# 3_SurvBot_RCU_MotorControl.net
KiCad netlist of a schematic drawn in Altium Designer
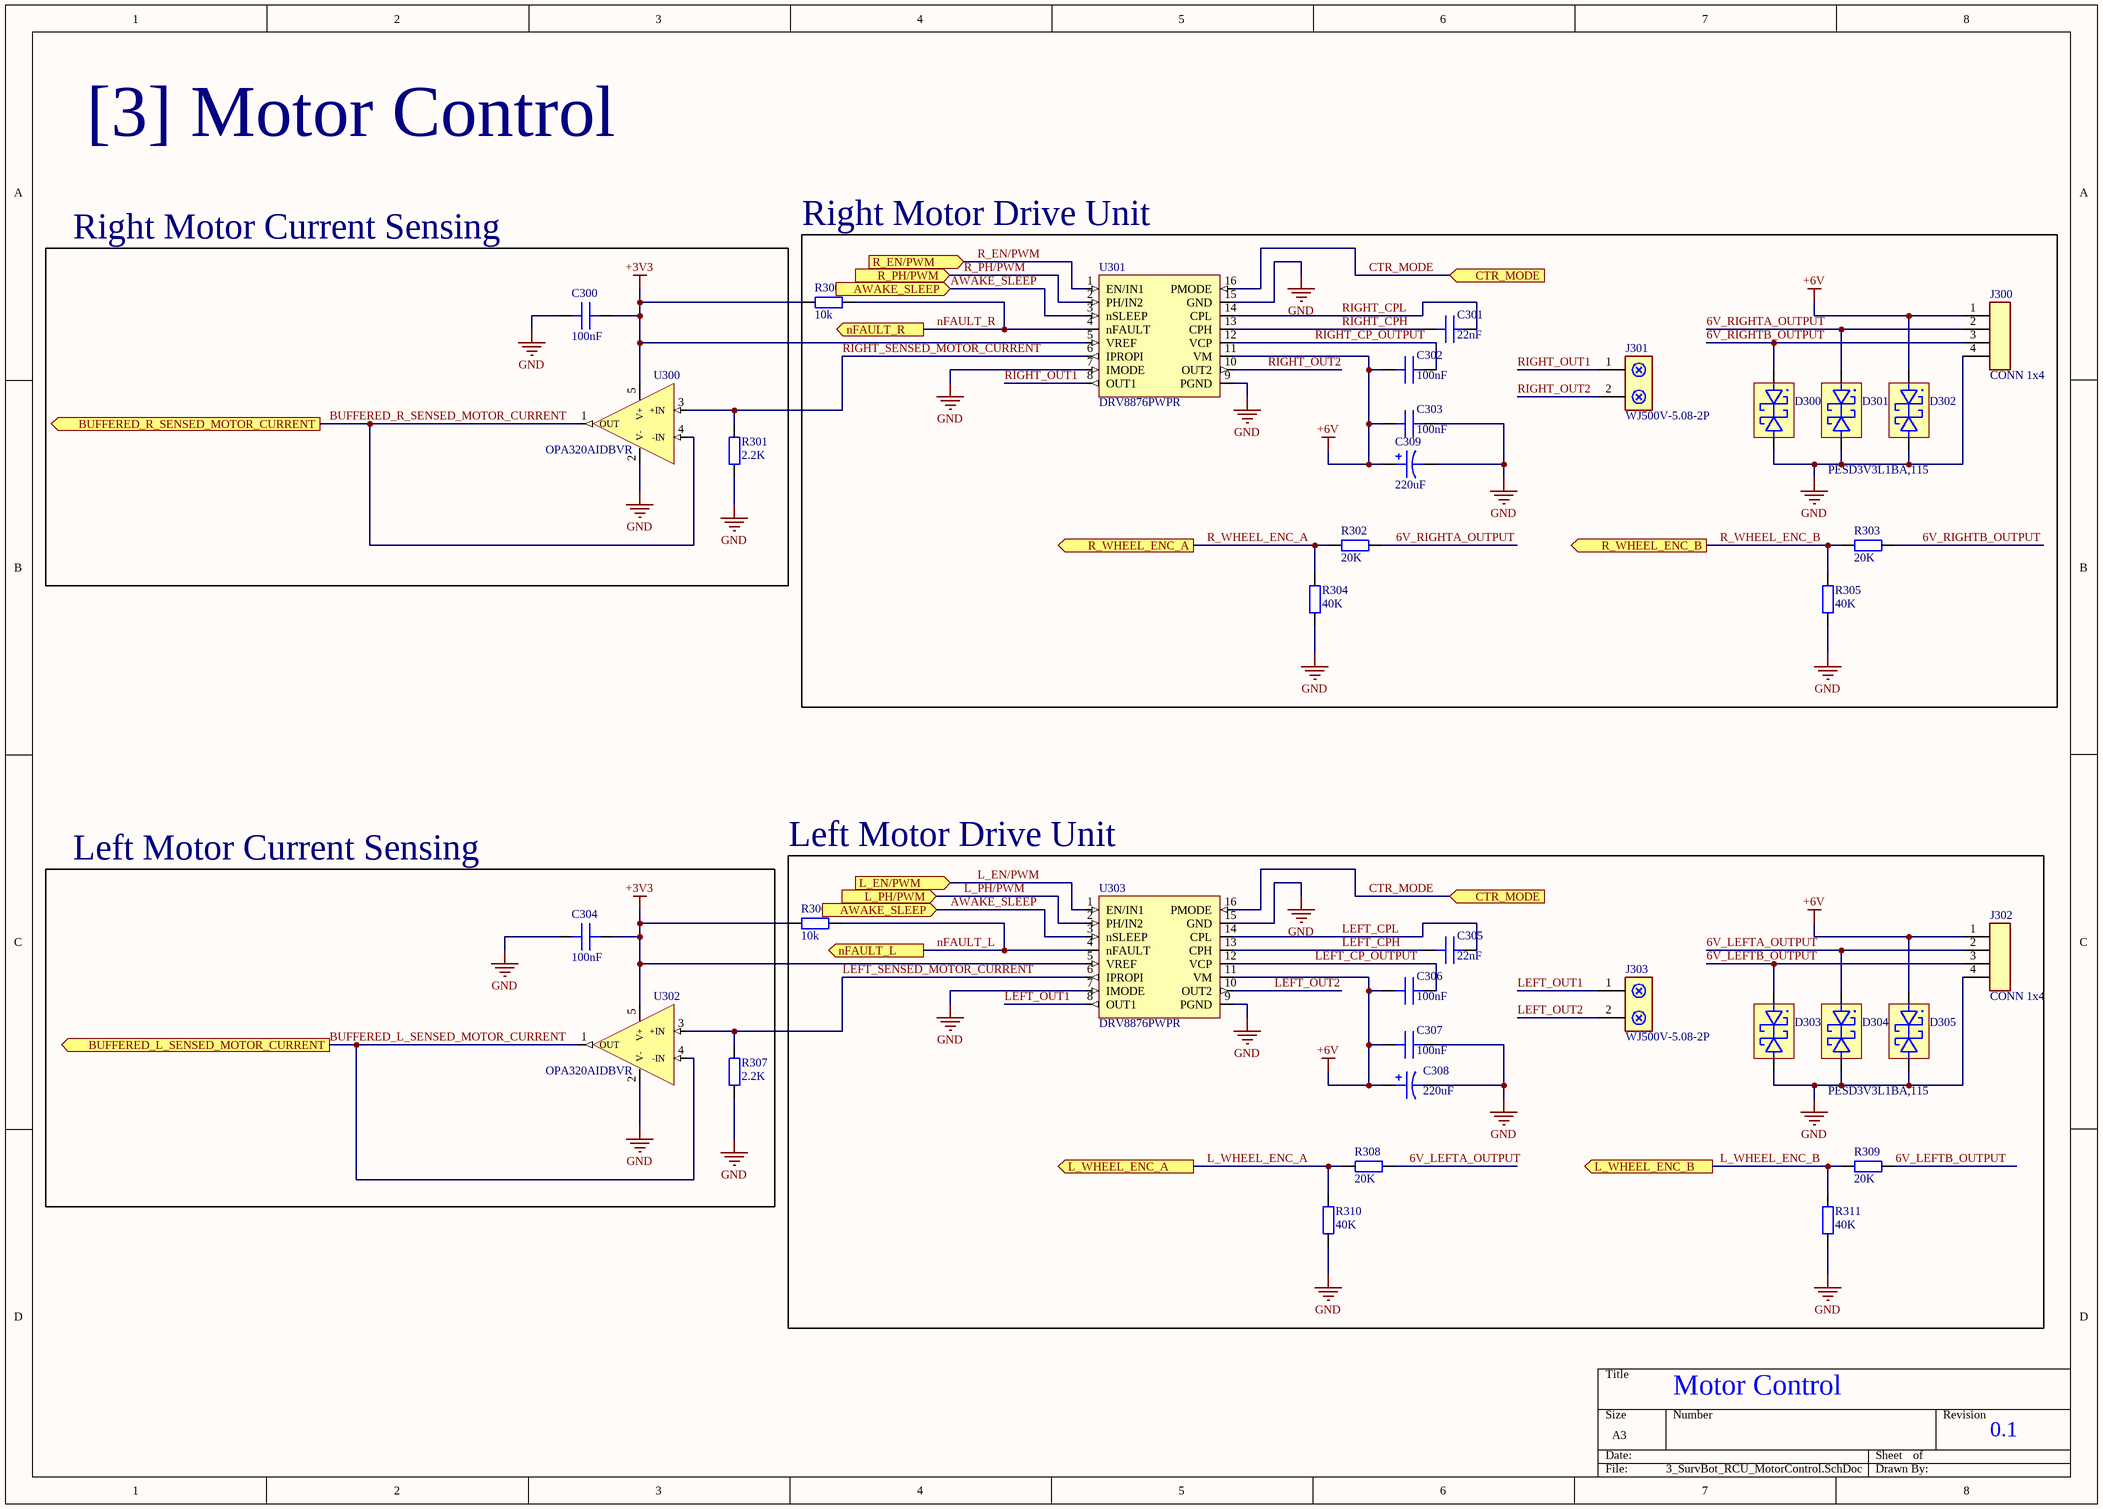
[diagram p0: 3_SurvBot_RCU_MotorControl.SchDoc]

(export (version "E")
  (design (tool "Eeschema 10.0.6"))
  (components
    (comp (ref "C300")
      (value "100nF")
      (footprint "CAP_0603")
      (description "0.1 µF ±10% 50V Ceramic Capacitor X7R 0603 (1608 Metric)")
      (fields (field (name "MANUFACTURER") "KEMET") (field (name "MANUFACTURER PART #") "C0603C104K5RACAUTO"))
      (libsource (lib "GhaniLibrary") (part "CAP_100nF-50V-10%-0603"))
    )
    (comp (ref "C301")
      (value "22nF")
      (footprint "CAP_0603")
      (description "0.022 µF ±10% 100V Ceramic Capacitor X7R 0603 (1608 Metric)")
      (fields
        (field (name "MANUFACTURER") "Murata Electronics")
        (field (name "MANUFACTURER PART #") "GCM188R72A223KA37D")
      )
      (libsource (lib "GhaniLibrary") (part "CAP_22nF_100V-10%-0603"))
    )
    (comp (ref "C302")
      (value "100nF")
      (footprint "CAP_0603")
      (description "0.1 µF ±10% 50V Ceramic Capacitor X7R 0603 (1608 Metric)")
      (fields (field (name "MANUFACTURER") "KEMET") (field (name "MANUFACTURER PART #") "C0603C104K5RACAUTO"))
      (libsource (lib "GhaniLibrary") (part "CAP_100nF-50V-10%-0603"))
    )
    (comp (ref "C303")
      (value "100nF")
      (footprint "CAP_0603")
      (description "0.1 µF ±10% 50V Ceramic Capacitor X7R 0603 (1608 Metric)")
      (fields (field (name "MANUFACTURER") "KEMET") (field (name "MANUFACTURER PART #") "C0603C104K5RACAUTO"))
      (libsource (lib "GhaniLibrary") (part "CAP_100nF-50V-10%-0603"))
    )
    (comp (ref "C304")
      (value "100nF")
      (footprint "CAP_0603")
      (description "0.1 µF ±10% 50V Ceramic Capacitor X7R 0603 (1608 Metric)")
      (fields (field (name "MANUFACTURER") "KEMET") (field (name "MANUFACTURER PART #") "C0603C104K5RACAUTO"))
      (libsource (lib "GhaniLibrary") (part "CAP_100nF-50V-10%-0603"))
    )
    (comp (ref "C305")
      (value "22nF")
      (footprint "CAP_0603")
      (description "0.022 µF ±10% 100V Ceramic Capacitor X7R 0603 (1608 Metric)")
      (fields
        (field (name "MANUFACTURER") "Murata Electronics")
        (field (name "MANUFACTURER PART #") "GCM188R72A223KA37D")
      )
      (libsource (lib "GhaniLibrary") (part "CAP_22nF_100V-10%-0603"))
    )
    (comp (ref "C306")
      (value "100nF")
      (footprint "CAP_0603")
      (description "0.1 µF ±10% 50V Ceramic Capacitor X7R 0603 (1608 Metric)")
      (fields (field (name "MANUFACTURER") "KEMET") (field (name "MANUFACTURER PART #") "C0603C104K5RACAUTO"))
      (libsource (lib "GhaniLibrary") (part "CAP_100nF-50V-10%-0603"))
    )
    (comp (ref "C307")
      (value "100nF")
      (footprint "CAP_0603")
      (description "0.1 µF ±10% 50V Ceramic Capacitor X7R 0603 (1608 Metric)")
      (fields (field (name "MANUFACTURER") "KEMET") (field (name "MANUFACTURER PART #") "C0603C104K5RACAUTO"))
      (libsource (lib "GhaniLibrary") (part "CAP_100nF-50V-10%-0603"))
    )
    (comp (ref "C308")
      (value "220uF")
      (footprint "CAP-THT-Radial__D8.0mmP3.5mm")
      (description "220 µF 35 V Aluminum Electrolytic Capacitors Radial, Can 8000 Hrs @ 105°C")
      (fields
        (field (name "MANUFACTURER") "Rubycon")
        (field (name "MANUFACTURER PART #") "35ZLH220MEFC8X11.5")
      )
      (libsource (lib "GhaniLibrary") (part "CAP_220uF-35V-20%_RADIAL-TH"))
    )
    (comp (ref "C309")
      (value "220uF")
      (footprint "CAP-THT-Radial__D8.0mmP3.5mm")
      (description "220 µF 35 V Aluminum Electrolytic Capacitors Radial, Can 8000 Hrs @ 105°C")
      (fields
        (field (name "MANUFACTURER") "Rubycon")
        (field (name "MANUFACTURER PART #") "35ZLH220MEFC8X11.5")
      )
      (libsource (lib "GhaniLibrary") (part "CAP_220uF-35V-20%_RADIAL-TH"))
    )
    (comp (ref "D300")
      (value "PESD3V3L1BA,115")
      (footprint "SC-76, SOD-323")
      (description "26V Clamp 18A (8/20µs) Ipp Tvs Diode Surface Mount SOD-323")
      (fields (field (name "MANUFACTURER") "Nexperia"))
      (libsource (lib "GhaniLibrary") (part "DIO-TVS_3.3V-26V-18A-SOD-323"))
    )
    (comp (ref "D301")
      (value "PESD3V3L1BA,115")
      (footprint "SC-76, SOD-323")
      (description "26V Clamp 18A (8/20µs) Ipp Tvs Diode Surface Mount SOD-323")
      (fields (field (name "MANUFACTURER") "Nexperia"))
      (libsource (lib "GhaniLibrary") (part "DIO-TVS_3.3V-26V-18A-SOD-323"))
    )
    (comp (ref "D302")
      (value "PESD3V3L1BA,115")
      (footprint "SC-76, SOD-323")
      (description "26V Clamp 18A (8/20µs) Ipp Tvs Diode Surface Mount SOD-323")
      (fields (field (name "MANUFACTURER") "Nexperia"))
      (libsource (lib "GhaniLibrary") (part "DIO-TVS_3.3V-26V-18A-SOD-323"))
    )
    (comp (ref "D303")
      (value "PESD3V3L1BA,115")
      (footprint "SC-76, SOD-323")
      (description "26V Clamp 18A (8/20µs) Ipp Tvs Diode Surface Mount SOD-323")
      (fields (field (name "MANUFACTURER") "Nexperia"))
      (libsource (lib "GhaniLibrary") (part "DIO-TVS_3.3V-26V-18A-SOD-323"))
    )
    (comp (ref "D304")
      (value "PESD3V3L1BA,115")
      (footprint "SC-76, SOD-323")
      (description "26V Clamp 18A (8/20µs) Ipp Tvs Diode Surface Mount SOD-323")
      (fields (field (name "MANUFACTURER") "Nexperia"))
      (libsource (lib "GhaniLibrary") (part "DIO-TVS_3.3V-26V-18A-SOD-323"))
    )
    (comp (ref "D305")
      (value "PESD3V3L1BA,115")
      (footprint "SC-76, SOD-323")
      (description "26V Clamp 18A (8/20µs) Ipp Tvs Diode Surface Mount SOD-323")
      (fields (field (name "MANUFACTURER") "Nexperia"))
      (libsource (lib "GhaniLibrary") (part "DIO-TVS_3.3V-26V-18A-SOD-323"))
    )
    (comp (ref "J300")
      (value "CONN 1x4")
      (footprint "2541FV-4P")
      (fields (field (name "MANUFACTURER") "HanElectricity") (field (name "MANUFACTURER PART #") "2541FV-4P"))
      (libsource (lib "GhaniLibrary") (part "CONN_4_HDR_0.1-2541FV-4P"))
    )
    (comp (ref "J301")
      (value "WJ500V-5.08-2P")
      (footprint "WJ500V-5.08-2P")
      (fields (field (name "MANUFACTURER") "Ningbo Kangnex Elec"))
      (libsource (lib "GhaniLibrary") (part "Terminal_Screw_5.08mm_2P"))
    )
    (comp (ref "J302")
      (value "CONN 1x4")
      (footprint "2541FV-4P")
      (fields (field (name "MANUFACTURER") "HanElectricity") (field (name "MANUFACTURER PART #") "2541FV-4P"))
      (libsource (lib "GhaniLibrary") (part "CONN_4_HDR_0.1-2541FV-4P"))
    )
    (comp (ref "J303")
      (value "WJ500V-5.08-2P")
      (footprint "WJ500V-5.08-2P")
      (fields (field (name "MANUFACTURER") "Ningbo Kangnex Elec"))
      (libsource (lib "GhaniLibrary") (part "Terminal_Screw_5.08mm_2P"))
    )
    (comp (ref "R300")
      (value "10k")
      (footprint "RES_0402")
      (description "10 kOhms ±1% 0.063W, 1/16W Chip Resistor 0402 (1005 Metric) Moisture Resistant Thick Film")
      (fields (field (name "MANUFACTURER") "YAGEO") (field (name "MANUFACTURER PART #") "RC0402FR-0710KL"))
      (libsource (lib "GhaniLibrary") (part "RES_10K-62.5mW-1%-0402"))
    )
    (comp (ref "R301")
      (value "2.2K")
      (footprint "RES_0603")
      (description "2.2 kOhms ±1% 0.1W, 1/10W Chip Resistor 0603 (1608 Metric) Moisture Resistant Thick Film")
      (fields (field (name "MANUFACTURER") "YAGEO") (field (name "MANUFACTURER PART #") "RC0603FR-072K2L"))
      (libsource (lib "GhaniLibrary") (part "RES_2.2K-100mW-1%-0603"))
    )
    (comp (ref "R302")
      (value "20K")
      (footprint "RES_0603")
      (description "20 kOhms ±1% 0.1W, 1/10W Chip Resistor 0603 (1608 Metric) Automotive AEC-Q200 Thick Film")
      (fields (field (name "MANUFACTURER") "PANASONIC") (field (name "MANUFACTURER PART #") "ERJ-3EKF2002V"))
      (libsource (lib "GhaniLibrary") (part "RES_20K-100mW-1%-0603"))
    )
    (comp (ref "R303")
      (value "20K")
      (footprint "RES_0603")
      (description "20 kOhms ±1% 0.1W, 1/10W Chip Resistor 0603 (1608 Metric) Automotive AEC-Q200 Thick Film")
      (fields (field (name "MANUFACTURER") "PANASONIC") (field (name "MANUFACTURER PART #") "ERJ-3EKF2002V"))
      (libsource (lib "GhaniLibrary") (part "RES_20K-100mW-1%-0603"))
    )
    (comp (ref "R304")
      (value "40K")
      (footprint "RES_0603")
      (fields (field (name "MANUFACTURER") "YAGEO") (field (name "MANUFACTURER PART #") "AT0603BRD0740KL"))
      (libsource (lib "GhaniLibrary") (part "RES_40K_100mW-1%-0603"))
    )
    (comp (ref "R305")
      (value "40K")
      (footprint "RES_0603")
      (fields (field (name "MANUFACTURER") "YAGEO") (field (name "MANUFACTURER PART #") "AT0603BRD0740KL"))
      (libsource (lib "GhaniLibrary") (part "RES_40K_100mW-1%-0603"))
    )
    (comp (ref "R306")
      (value "10k")
      (footprint "RES_0402")
      (description "10 kOhms ±1% 0.063W, 1/16W Chip Resistor 0402 (1005 Metric) Moisture Resistant Thick Film")
      (fields (field (name "MANUFACTURER") "YAGEO") (field (name "MANUFACTURER PART #") "RC0402FR-0710KL"))
      (libsource (lib "GhaniLibrary") (part "RES_10K-62.5mW-1%-0402"))
    )
    (comp (ref "R307")
      (value "2.2K")
      (footprint "RES_0603")
      (description "2.2 kOhms ±1% 0.1W, 1/10W Chip Resistor 0603 (1608 Metric) Moisture Resistant Thick Film")
      (fields (field (name "MANUFACTURER") "YAGEO") (field (name "MANUFACTURER PART #") "RC0603FR-072K2L"))
      (libsource (lib "GhaniLibrary") (part "RES_2.2K-100mW-1%-0603"))
    )
    (comp (ref "R308")
      (value "20K")
      (footprint "RES_0603")
      (description "20 kOhms ±1% 0.1W, 1/10W Chip Resistor 0603 (1608 Metric) Automotive AEC-Q200 Thick Film")
      (fields (field (name "MANUFACTURER") "PANASONIC") (field (name "MANUFACTURER PART #") "ERJ-3EKF2002V"))
      (libsource (lib "GhaniLibrary") (part "RES_20K-100mW-1%-0603"))
    )
    (comp (ref "R309")
      (value "20K")
      (footprint "RES_0603")
      (description "20 kOhms ±1% 0.1W, 1/10W Chip Resistor 0603 (1608 Metric) Automotive AEC-Q200 Thick Film")
      (fields (field (name "MANUFACTURER") "PANASONIC") (field (name "MANUFACTURER PART #") "ERJ-3EKF2002V"))
      (libsource (lib "GhaniLibrary") (part "RES_20K-100mW-1%-0603"))
    )
    (comp (ref "R310")
      (value "40K")
      (footprint "RES_0603")
      (fields (field (name "MANUFACTURER") "YAGEO") (field (name "MANUFACTURER PART #") "AT0603BRD0740KL"))
      (libsource (lib "GhaniLibrary") (part "RES_40K_100mW-1%-0603"))
    )
    (comp (ref "R311")
      (value "40K")
      (footprint "RES_0603")
      (fields (field (name "MANUFACTURER") "YAGEO") (field (name "MANUFACTURER PART #") "AT0603BRD0740KL"))
      (libsource (lib "GhaniLibrary") (part "RES_40K_100mW-1%-0603"))
    )
    (comp (ref "U300")
      (value "OPA320AIDBVR")
      (footprint "SOT-23-5")
      (description "General Purpose Amplifier 1 Circuit Rail-to-Rail SOT-23-5")
      (fields (field (name "MANUFACTURER") "Texas Instruments"))
      (libsource (lib "GhaniLibrary") (part "OPAMP-OPA320_R2R_SOT23-5"))
    )
    (comp (ref "U301")
      (value "DRV8876PWPR")
      (footprint "16-HTSSOP")
      (description "DRV8876 H-Bridge Motor Driver With Integrated Current Sense and Regulation 16-HTSSOP")
      (fields (field (name "MANUFACTURER") "Texas Instruments"))
      (libsource (lib "GhaniLibrary") (part "MTRDRV-DRV8876-HBridge_4.5-37V_3.5A"))
    )
    (comp (ref "U302")
      (value "OPA320AIDBVR")
      (footprint "SOT-23-5")
      (description "General Purpose Amplifier 1 Circuit Rail-to-Rail SOT-23-5")
      (fields (field (name "MANUFACTURER") "Texas Instruments"))
      (libsource (lib "GhaniLibrary") (part "OPAMP-OPA320_R2R_SOT23-5"))
    )
    (comp (ref "U303")
      (value "DRV8876PWPR")
      (footprint "16-HTSSOP")
      (description "DRV8876 H-Bridge Motor Driver With Integrated Current Sense and Regulation 16-HTSSOP")
      (fields (field (name "MANUFACTURER") "Texas Instruments"))
      (libsource (lib "GhaniLibrary") (part "MTRDRV-DRV8876-HBridge_4.5-37V_3.5A"))
    )
  )
  (nets
    (net (code "1") (name "+3V3") (class "Default")
      (node (ref "C300") (pin "1") (pinfunction "0_1") (pintype "passive"))
      (node (ref "C304") (pin "1") (pinfunction "0_1") (pintype "passive"))
      (node (ref "R300") (pin "1") (pinfunction "1_1") (pintype "passive"))
      (node (ref "R306") (pin "1") (pinfunction "1_1") (pintype "passive"))
      (node (ref "U300") (pin "5") (pinfunction "V+_5") (pintype "power_in"))
      (node (ref "U301") (pin "5") (pinfunction "VREF_5") (pintype "input"))
      (node (ref "U302") (pin "5") (pinfunction "V+_5") (pintype "power_in"))
      (node (ref "U303") (pin "5") (pinfunction "VREF_5") (pintype "input"))
    )
    (net (code "2") (name "+6V") (class "Default")
      (node (ref "C302") (pin "2") (pinfunction "0_2") (pintype "passive"))
      (node (ref "C303") (pin "2") (pinfunction "0_2") (pintype "passive"))
      (node (ref "C306") (pin "2") (pinfunction "0_2") (pintype "passive"))
      (node (ref "C307") (pin "2") (pinfunction "0_2") (pintype "passive"))
      (node (ref "C308") (pin "1") (pinfunction "0_1") (pintype "passive"))
      (node (ref "C309") (pin "1") (pinfunction "0_1") (pintype "passive"))
      (node (ref "D302") (pin "K1") (pinfunction "1_K1") (pintype "passive"))
      (node (ref "D305") (pin "K1") (pinfunction "1_K1") (pintype "passive"))
      (node (ref "J300") (pin "1") (pintype "passive"))
      (node (ref "J302") (pin "1") (pintype "passive"))
      (node (ref "U301") (pin "11") (pinfunction "VM_11") (pintype "power_in"))
      (node (ref "U303") (pin "11") (pinfunction "VM_11") (pintype "power_in"))
    )
    (net (code "3") (name "/6V_LEFTA_OUTPUT") (class "Default")
      (node (ref "D304") (pin "K1") (pinfunction "1_K1") (pintype "passive"))
      (node (ref "J302") (pin "2") (pinfunction "2_2") (pintype "passive"))
      (node (ref "R308") (pin "2") (pinfunction "2_2") (pintype "passive"))
    )
    (net (code "4") (name "/6V_LEFTB_OUTPUT") (class "Default")
      (node (ref "D303") (pin "K1") (pinfunction "1_K1") (pintype "passive"))
      (node (ref "J302") (pin "3") (pinfunction "3_3") (pintype "passive"))
      (node (ref "R309") (pin "2") (pinfunction "2_2") (pintype "passive"))
    )
    (net (code "5") (name "/6V_RIGHTA_OUTPUT") (class "Default")
      (node (ref "D301") (pin "K1") (pinfunction "1_K1") (pintype "passive"))
      (node (ref "J300") (pin "2") (pinfunction "2_2") (pintype "passive"))
      (node (ref "R302") (pin "2") (pinfunction "2_2") (pintype "passive"))
    )
    (net (code "6") (name "/6V_RIGHTB_OUTPUT") (class "Default")
      (node (ref "D300") (pin "K1") (pinfunction "1_K1") (pintype "passive"))
      (node (ref "J300") (pin "3") (pinfunction "3_3") (pintype "passive"))
      (node (ref "R303") (pin "2") (pinfunction "2_2") (pintype "passive"))
    )
    (net (code "7") (name "/AWAKE_SLEEP") (class "Default")
      (node (ref "U301") (pin "3") (pinfunction "nSLEEP_3") (pintype "input"))
      (node (ref "U303") (pin "3") (pinfunction "nSLEEP_3") (pintype "input"))
    )
    (net (code "8") (name "/BUFFERED_L_SENSED_MOTOR_CURRENT") (class "Default")
      (node (ref "U302") (pin "1") (pinfunction "OUT_1") (pintype "output"))
      (node (ref "U302") (pin "4") (pinfunction "-IN_4") (pintype "input"))
    )
    (net (code "9") (name "/BUFFERED_R_SENSED_MOTOR_CURRENT") (class "Default")
      (node (ref "U300") (pin "1") (pinfunction "OUT_1") (pintype "output"))
      (node (ref "U300") (pin "4") (pinfunction "-IN_4") (pintype "input"))
    )
    (net (code "10") (name "/CTR_MODE") (class "Default")
      (node (ref "U301") (pin "16") (pinfunction "PMODE_16") (pintype "input"))
      (node (ref "U303") (pin "16") (pinfunction "PMODE_16") (pintype "input"))
    )
    (net (code "11") (name "/LEFT_CPH") (class "Default")
      (node (ref "C305") (pin "1") (pinfunction "0_1") (pintype "passive"))
      (node (ref "U303") (pin "13") (pinfunction "CPH_13") (pintype "power_in"))
    )
    (net (code "12") (name "/LEFT_CPL") (class "Default")
      (node (ref "C305") (pin "2") (pinfunction "0_2") (pintype "passive"))
      (node (ref "U303") (pin "14") (pinfunction "CPL_14") (pintype "power_in"))
    )
    (net (code "13") (name "/LEFT_CP_OUTPUT") (class "Default")
      (node (ref "C306") (pin "1") (pinfunction "0_1") (pintype "passive"))
      (node (ref "U303") (pin "12") (pinfunction "VCP_12") (pintype "power_in"))
    )
    (net (code "14") (name "/LEFT_OUT1") (class "Default")
      (node (ref "J303") (pin "1") (pintype "passive"))
      (node (ref "U303") (pin "8") (pinfunction "OUT1_8") (pintype "output"))
    )
    (net (code "15") (name "/LEFT_OUT2") (class "Default")
      (node (ref "J303") (pin "2") (pinfunction "2_2") (pintype "passive"))
      (node (ref "U303") (pin "10") (pinfunction "OUT2_10") (pintype "output"))
    )
    (net (code "16") (name "/LEFT_SENSED_MOTOR_CURRENT") (class "Default")
      (node (ref "R307") (pin "2") (pinfunction "2_2") (pintype "passive"))
      (node (ref "U302") (pin "3") (pinfunction "+IN_3") (pintype "input"))
      (node (ref "U303") (pin "6") (pinfunction "IPROPI_6") (pintype "output"))
    )
    (net (code "17") (name "/L_EN{slash}PWM") (class "Default")
      (node (ref "U303") (pin "1") (pinfunction "EN/IN1_1") (pintype "input"))
    )
    (net (code "18") (name "/L_PH{slash}PWM") (class "Default")
      (node (ref "U303") (pin "2") (pinfunction "PH/IN2_2") (pintype "input"))
    )
    (net (code "19") (name "/L_WHEEL_ENC_A") (class "Default")
      (node (ref "R308") (pin "1") (pinfunction "1_1") (pintype "passive"))
      (node (ref "R310") (pin "2") (pinfunction "2_2") (pintype "passive"))
    )
    (net (code "20") (name "/L_WHEEL_ENC_B") (class "Default")
      (node (ref "R309") (pin "1") (pinfunction "1_1") (pintype "passive"))
      (node (ref "R311") (pin "2") (pinfunction "2_2") (pintype "passive"))
    )
    (net (code "21") (name "/RIGHT_CPH") (class "Default")
      (node (ref "C301") (pin "1") (pinfunction "0_1") (pintype "passive"))
      (node (ref "U301") (pin "13") (pinfunction "CPH_13") (pintype "power_in"))
    )
    (net (code "22") (name "/RIGHT_CPL") (class "Default")
      (node (ref "C301") (pin "2") (pinfunction "0_2") (pintype "passive"))
      (node (ref "U301") (pin "14") (pinfunction "CPL_14") (pintype "power_in"))
    )
    (net (code "23") (name "/RIGHT_CP_OUTPUT") (class "Default")
      (node (ref "C302") (pin "1") (pinfunction "0_1") (pintype "passive"))
      (node (ref "U301") (pin "12") (pinfunction "VCP_12") (pintype "power_in"))
    )
    (net (code "24") (name "/RIGHT_OUT1") (class "Default")
      (node (ref "J301") (pin "1") (pintype "passive"))
      (node (ref "U301") (pin "8") (pinfunction "OUT1_8") (pintype "output"))
    )
    (net (code "25") (name "/RIGHT_OUT2") (class "Default")
      (node (ref "J301") (pin "2") (pinfunction "2_2") (pintype "passive"))
      (node (ref "U301") (pin "10") (pinfunction "OUT2_10") (pintype "output"))
    )
    (net (code "26") (name "/RIGHT_SENSED_MOTOR_CURRENT") (class "Default")
      (node (ref "R301") (pin "2") (pinfunction "2_2") (pintype "passive"))
      (node (ref "U300") (pin "3") (pinfunction "+IN_3") (pintype "input"))
      (node (ref "U301") (pin "6") (pinfunction "IPROPI_6") (pintype "output"))
    )
    (net (code "27") (name "/R_EN{slash}PWM") (class "Default")
      (node (ref "U301") (pin "1") (pinfunction "EN/IN1_1") (pintype "input"))
    )
    (net (code "28") (name "/R_PH{slash}PWM") (class "Default")
      (node (ref "U301") (pin "2") (pinfunction "PH/IN2_2") (pintype "input"))
    )
    (net (code "29") (name "/R_WHEEL_ENC_A") (class "Default")
      (node (ref "R302") (pin "1") (pinfunction "1_1") (pintype "passive"))
      (node (ref "R304") (pin "2") (pinfunction "2_2") (pintype "passive"))
    )
    (net (code "30") (name "/R_WHEEL_ENC_B") (class "Default")
      (node (ref "R303") (pin "1") (pinfunction "1_1") (pintype "passive"))
      (node (ref "R305") (pin "2") (pinfunction "2_2") (pintype "passive"))
    )
    (net (code "31") (name "/nFAULT_L") (class "Default")
      (node (ref "R306") (pin "2") (pinfunction "2_2") (pintype "passive"))
      (node (ref "U303") (pin "4") (pinfunction "nFAULT_4") (pintype "open_collector"))
    )
    (net (code "32") (name "/nFAULT_R") (class "Default")
      (node (ref "R300") (pin "2") (pinfunction "2_2") (pintype "passive"))
      (node (ref "U301") (pin "4") (pinfunction "nFAULT_4") (pintype "open_collector"))
    )
    (net (code "33") (name "GND") (class "Default")
      (node (ref "C300") (pin "2") (pinfunction "0_2") (pintype "passive"))
      (node (ref "C303") (pin "1") (pinfunction "0_1") (pintype "passive"))
      (node (ref "C304") (pin "2") (pinfunction "0_2") (pintype "passive"))
      (node (ref "C307") (pin "1") (pinfunction "0_1") (pintype "passive"))
      (node (ref "C308") (pin "2") (pinfunction "0_2") (pintype "passive"))
      (node (ref "C309") (pin "2") (pinfunction "0_2") (pintype "passive"))
      (node (ref "D300") (pin "K2") (pinfunction "2_K2") (pintype "passive"))
      (node (ref "D301") (pin "K2") (pinfunction "2_K2") (pintype "passive"))
      (node (ref "D302") (pin "K2") (pinfunction "2_K2") (pintype "passive"))
      (node (ref "D303") (pin "K2") (pinfunction "2_K2") (pintype "passive"))
      (node (ref "D304") (pin "K2") (pinfunction "2_K2") (pintype "passive"))
      (node (ref "D305") (pin "K2") (pinfunction "2_K2") (pintype "passive"))
      (node (ref "J300") (pin "4") (pinfunction "4_4") (pintype "passive"))
      (node (ref "J302") (pin "4") (pinfunction "4_4") (pintype "passive"))
      (node (ref "R301") (pin "1") (pinfunction "1_1") (pintype "passive"))
      (node (ref "R304") (pin "1") (pinfunction "1_1") (pintype "passive"))
      (node (ref "R305") (pin "1") (pinfunction "1_1") (pintype "passive"))
      (node (ref "R307") (pin "1") (pinfunction "1_1") (pintype "passive"))
      (node (ref "R310") (pin "1") (pinfunction "1_1") (pintype "passive"))
      (node (ref "R311") (pin "1") (pinfunction "1_1") (pintype "passive"))
      (node (ref "U300") (pin "2") (pinfunction "V-_2") (pintype "power_in"))
      (node (ref "U301") (pin "15") (pinfunction "GND_15") (pintype "power_in"))
      (node (ref "U301") (pin "7") (pinfunction "IMODE_7") (pintype "input"))
      (node (ref "U301") (pin "9") (pinfunction "PGND_9") (pintype "power_in"))
      (node (ref "U302") (pin "2") (pinfunction "V-_2") (pintype "power_in"))
      (node (ref "U303") (pin "15") (pinfunction "GND_15") (pintype "power_in"))
      (node (ref "U303") (pin "7") (pinfunction "IMODE_7") (pintype "input"))
      (node (ref "U303") (pin "9") (pinfunction "PGND_9") (pintype "power_in"))
    )
  )
)
